# raspiPowerControl.net
KiCad netlist of a schematic drawn in EAGLE
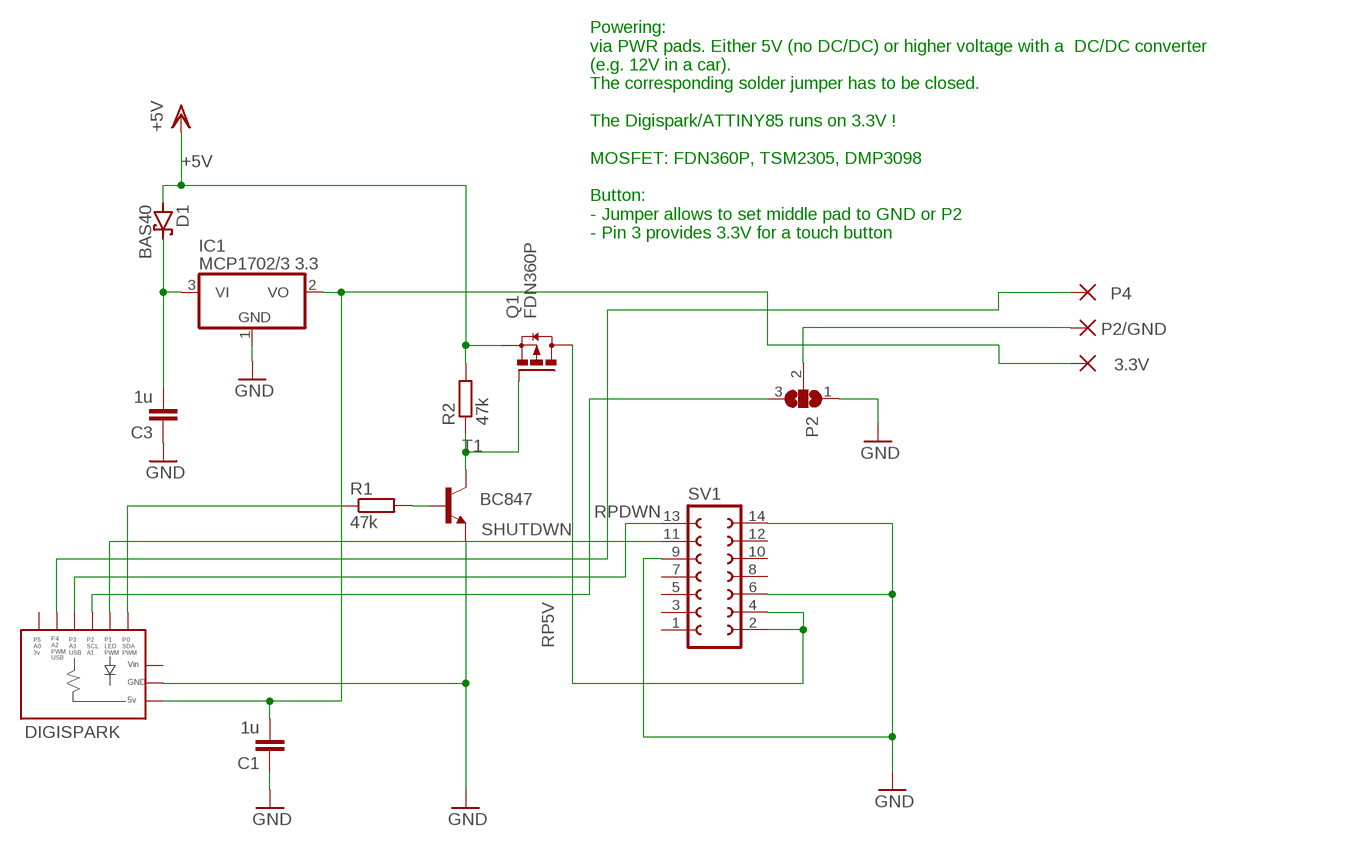
[diagram p0: schematic, sheet 1]
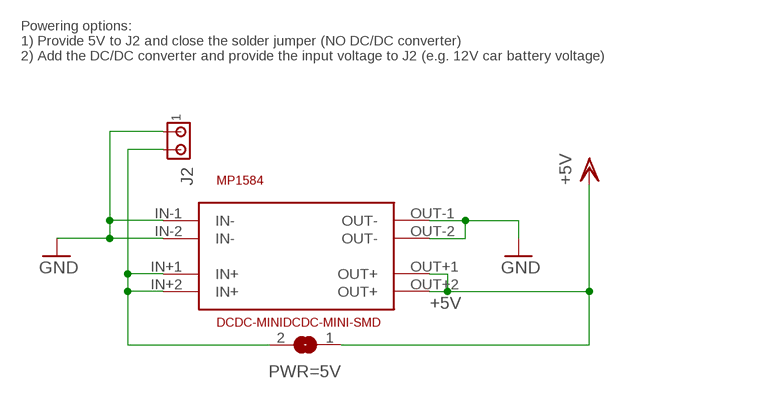
[diagram p1: schematic, sheet 2]

(export (version "E")
  (design (tool "Eeschema 10.0.6"))
  (components
    (comp (ref "3.3V")
      (value "WIREPADSMD5-1,8")
      (footprint "eagle-import:5-1,8")
      (libsource (lib "eagle-import") (part "WIREPADSMD5-1,8"))
    )
    (comp (ref "C1")
      (value "1u")
      (footprint "eagle-import:C0805")
      (libsource (lib "eagle-import") (part "C-EUC0805"))
    )
    (comp (ref "C3")
      (value "1u")
      (footprint "eagle-import:C0805")
      (libsource (lib "eagle-import") (part "C-EUC0805"))
    )
    (comp (ref "D1")
      (value "BAS40")
      (footprint "eagle-import:SOT23")
      (libsource (lib "eagle-import") (part "BAS40"))
    )
    (comp (ref "DIGISPARK")
      (value "DIGISPARKDIGISPARK-SMD")
      (footprint "eagle-import:DIGISPARK-SMD")
      (libsource (lib "eagle-import") (part "DIGISPARKDIGISPARK-SMD"))
    )
    (comp (ref "IC1")
      (value "MCP1702/3 3.3")
      (footprint "eagle-import:SOT23")
      (libsource (lib "eagle-import") (part "MCP1703CB"))
    )
    (comp (ref "P2")
      (value "SJ2W")
      (footprint "eagle-import:SJ_2")
      (libsource (lib "eagle-import") (part "SJ2W"))
    )
    (comp (ref "P2/GND")
      (value "WIREPADSMD5-1,8")
      (footprint "eagle-import:5-1,8")
      (libsource (lib "eagle-import") (part "WIREPADSMD5-1,8"))
    )
    (comp (ref "P4")
      (value "WIREPADSMD5-1,8")
      (footprint "eagle-import:5-1,8")
      (libsource (lib "eagle-import") (part "WIREPADSMD5-1,8"))
    )
    (comp (ref "Q1")
      (value "FDN360P")
      (footprint "eagle-import:SUPER-SOT3")
      (libsource (lib "eagle-import") (part "FDN360P"))
    )
    (comp (ref "R1")
      (value "47k")
      (footprint "eagle-import:M0805")
      (libsource (lib "eagle-import") (part "R-EU_M0805"))
    )
    (comp (ref "R2")
      (value "47k")
      (footprint "eagle-import:M0805")
      (libsource (lib "eagle-import") (part "R-EU_M0805"))
    )
    (comp (ref "SV1")
      (value "FE07-2")
      (footprint "eagle-import:FE07-2")
      (libsource (lib "eagle-import") (part "FE07-2"))
    )
    (comp (ref "T1")
      (value "BC847")
      (footprint "eagle-import:SOT23")
      (libsource (lib "eagle-import") (part "BC847"))
    )
    (comp (ref "J2")
      (value "MTA02-100")
      (footprint "eagle-import:10X02MTA")
      (libsource (lib "eagle-import") (part "MTA02-100"))
    )
    (comp (ref "MP1584")
      (value "DCDC-MINIDCDC-MINI-SMD")
      (footprint "eagle-import:DCDC-MINI-SMD")
      (libsource (lib "eagle-import") (part "DCDC-MINIDCDC-MINI-SMD"))
    )
    (comp (ref "PWR=5V")
      (value "SJ")
      (footprint "eagle-import:SJ")
      (libsource (lib "eagle-import") (part "SJ"))
    )
  )
  (nets
    (net (code "1") (name "+5V") (class "Default")
      (node (ref "D1") (pin "1") (pinfunction "A_1") (pintype "passive"))
      (node (ref "MP1584") (pin "OUT+1") (pinfunction "OUT+_OUT+1") (pintype "power_in"))
      (node (ref "MP1584") (pin "OUT+2") (pinfunction "OUT+_OUT+2") (pintype "power_in"))
      (node (ref "PWR=5V") (pin "1") (pinfunction "1_1") (pintype "passive"))
      (node (ref "Q1") (pin "2") (pinfunction "S_2") (pintype "passive"))
      (node (ref "R2") (pin "2") (pinfunction "2_2") (pintype "passive"))
    )
    (net (code "2") (name "GND") (class "Default")
      (node (ref "C1") (pin "1") (pinfunction "1_1") (pintype "passive"))
      (node (ref "C3") (pin "1") (pinfunction "1_1") (pintype "passive"))
      (node (ref "DIGISPARK") (pin "GND") (pinfunction "GND_GND") (pintype "power_in"))
      (node (ref "IC1") (pin "1") (pinfunction "GND_1") (pintype "passive"))
      (node (ref "J2") (pin "1") (pinfunction "1_1") (pintype "passive"))
      (node (ref "MP1584") (pin "IN-1") (pinfunction "IN-_IN-1") (pintype "power_in"))
      (node (ref "MP1584") (pin "IN-2") (pinfunction "IN-_IN-2") (pintype "power_in"))
      (node (ref "MP1584") (pin "OUT-1") (pinfunction "OUT-_OUT-1") (pintype "power_in"))
      (node (ref "MP1584") (pin "OUT-2") (pinfunction "OUT-_OUT-2") (pintype "power_in"))
      (node (ref "P2") (pin "1") (pinfunction "1_1") (pintype "passive"))
      (node (ref "SV1") (pin "14") (pinfunction "14_14") (pintype "passive"))
      (node (ref "SV1") (pin "6") (pinfunction "6_6") (pintype "passive"))
      (node (ref "SV1") (pin "9") (pinfunction "9_9") (pintype "passive"))
      (node (ref "T1") (pin "2") (pinfunction "E_2") (pintype "passive"))
    )
    (net (code "3") (name "Net-(3.3V-P)") (class "Default")
      (node (ref "3.3V") (pin "1") (pinfunction "P_1") (pintype "passive"))
      (node (ref "C1") (pin "2") (pinfunction "2_2") (pintype "passive"))
      (node (ref "DIGISPARK") (pin "5V") (pinfunction "5V_5V") (pintype "power_in"))
      (node (ref "IC1") (pin "2") (pinfunction "VO_2") (pintype "passive"))
    )
    (net (code "4") (name "Net-(D1-C)") (class "Default")
      (node (ref "C3") (pin "2") (pinfunction "2_2") (pintype "passive"))
      (node (ref "D1") (pin "3") (pinfunction "C_3") (pintype "passive"))
      (node (ref "IC1") (pin "3") (pinfunction "VI_3") (pintype "input"))
    )
    (net (code "5") (name "Net-(DIGISPARK-PadP0)") (class "Default")
      (node (ref "DIGISPARK") (pin "P0") (pinfunction "P0_P0") (pintype "bidirectional"))
      (node (ref "R1") (pin "1") (pinfunction "1_1") (pintype "passive"))
    )
    (net (code "6") (name "Net-(DIGISPARK-PadP2)") (class "Default")
      (node (ref "DIGISPARK") (pin "P2") (pinfunction "P2_P2") (pintype "bidirectional"))
      (node (ref "P2") (pin "3") (pinfunction "3_3") (pintype "passive"))
    )
    (net (code "7") (name "Net-(J2-Pad2)") (class "Default")
      (node (ref "J2") (pin "2") (pinfunction "2_2") (pintype "passive"))
      (node (ref "MP1584") (pin "IN+1") (pinfunction "IN+_IN+1") (pintype "power_in"))
      (node (ref "MP1584") (pin "IN+2") (pinfunction "IN+_IN+2") (pintype "power_in"))
      (node (ref "PWR=5V") (pin "2") (pinfunction "2_2") (pintype "passive"))
    )
    (net (code "8") (name "Net-(P2/GND-P)") (class "Default")
      (node (ref "P2") (pin "2") (pinfunction "2_2") (pintype "passive"))
      (node (ref "P2/GND") (pin "1") (pinfunction "P_1") (pintype "passive"))
    )
    (net (code "9") (name "Net-(P4-P)") (class "Default")
      (node (ref "DIGISPARK") (pin "P4") (pinfunction "P4_P4") (pintype "bidirectional"))
      (node (ref "P4") (pin "1") (pinfunction "P_1") (pintype "passive"))
    )
    (net (code "10") (name "Net-(Q1-G)") (class "Default")
      (node (ref "Q1") (pin "1") (pinfunction "G_1") (pintype "passive"))
      (node (ref "R2") (pin "1") (pinfunction "1_1") (pintype "passive"))
      (node (ref "T1") (pin "3") (pinfunction "C_3") (pintype "passive"))
    )
    (net (code "11") (name "Net-(T1-B)") (class "Default")
      (node (ref "R1") (pin "2") (pinfunction "2_2") (pintype "passive"))
      (node (ref "T1") (pin "1") (pinfunction "B_1") (pintype "passive"))
    )
    (net (code "12") (name "RP5V") (class "Default")
      (node (ref "Q1") (pin "3") (pinfunction "D_3") (pintype "passive"))
      (node (ref "SV1") (pin "2") (pinfunction "2_2") (pintype "passive"))
      (node (ref "SV1") (pin "4") (pinfunction "4_4") (pintype "passive"))
    )
    (net (code "13") (name "RPDWN") (class "Default")
      (node (ref "DIGISPARK") (pin "P3") (pinfunction "P3_P3") (pintype "bidirectional"))
      (node (ref "SV1") (pin "13") (pinfunction "13_13") (pintype "passive"))
    )
    (net (code "14") (name "SHUTDWN") (class "Default")
      (node (ref "DIGISPARK") (pin "P1") (pinfunction "P1_P1") (pintype "bidirectional"))
      (node (ref "SV1") (pin "11") (pinfunction "11_11") (pintype "passive"))
    )
    (net (code "15") (name "VIN") (class "Default")
      (node (ref "DIGISPARK") (pin "VIN") (pinfunction "VIN_VIN") (pintype "power_in"))
    )
    (net (code "16") (name "unconnected-(DIGISPARK-PadP5)") (class "Default")
      (node (ref "DIGISPARK") (pin "P5") (pinfunction "P5_P5") (pintype "bidirectional"))
    )
    (net (code "17") (name "unconnected-(SV1-Pad1)") (class "Default")
      (node (ref "SV1") (pin "1") (pinfunction "1_1") (pintype "passive"))
    )
    (net (code "18") (name "unconnected-(SV1-Pad3)") (class "Default")
      (node (ref "SV1") (pin "3") (pinfunction "3_3") (pintype "passive"))
    )
    (net (code "19") (name "unconnected-(SV1-Pad5)") (class "Default")
      (node (ref "SV1") (pin "5") (pinfunction "5_5") (pintype "passive"))
    )
    (net (code "20") (name "unconnected-(SV1-Pad7)") (class "Default")
      (node (ref "SV1") (pin "7") (pinfunction "7_7") (pintype "passive"))
    )
    (net (code "21") (name "unconnected-(SV1-Pad8)") (class "Default")
      (node (ref "SV1") (pin "8") (pinfunction "8_8") (pintype "passive"))
    )
    (net (code "22") (name "unconnected-(SV1-Pad10)") (class "Default")
      (node (ref "SV1") (pin "10") (pinfunction "10_10") (pintype "passive"))
    )
    (net (code "23") (name "unconnected-(SV1-Pad12)") (class "Default")
      (node (ref "SV1") (pin "12") (pinfunction "12_12") (pintype "passive"))
    )
  )
)
